# FPGA_Power.net
KiCad netlist of a schematic drawn in Altium Designer
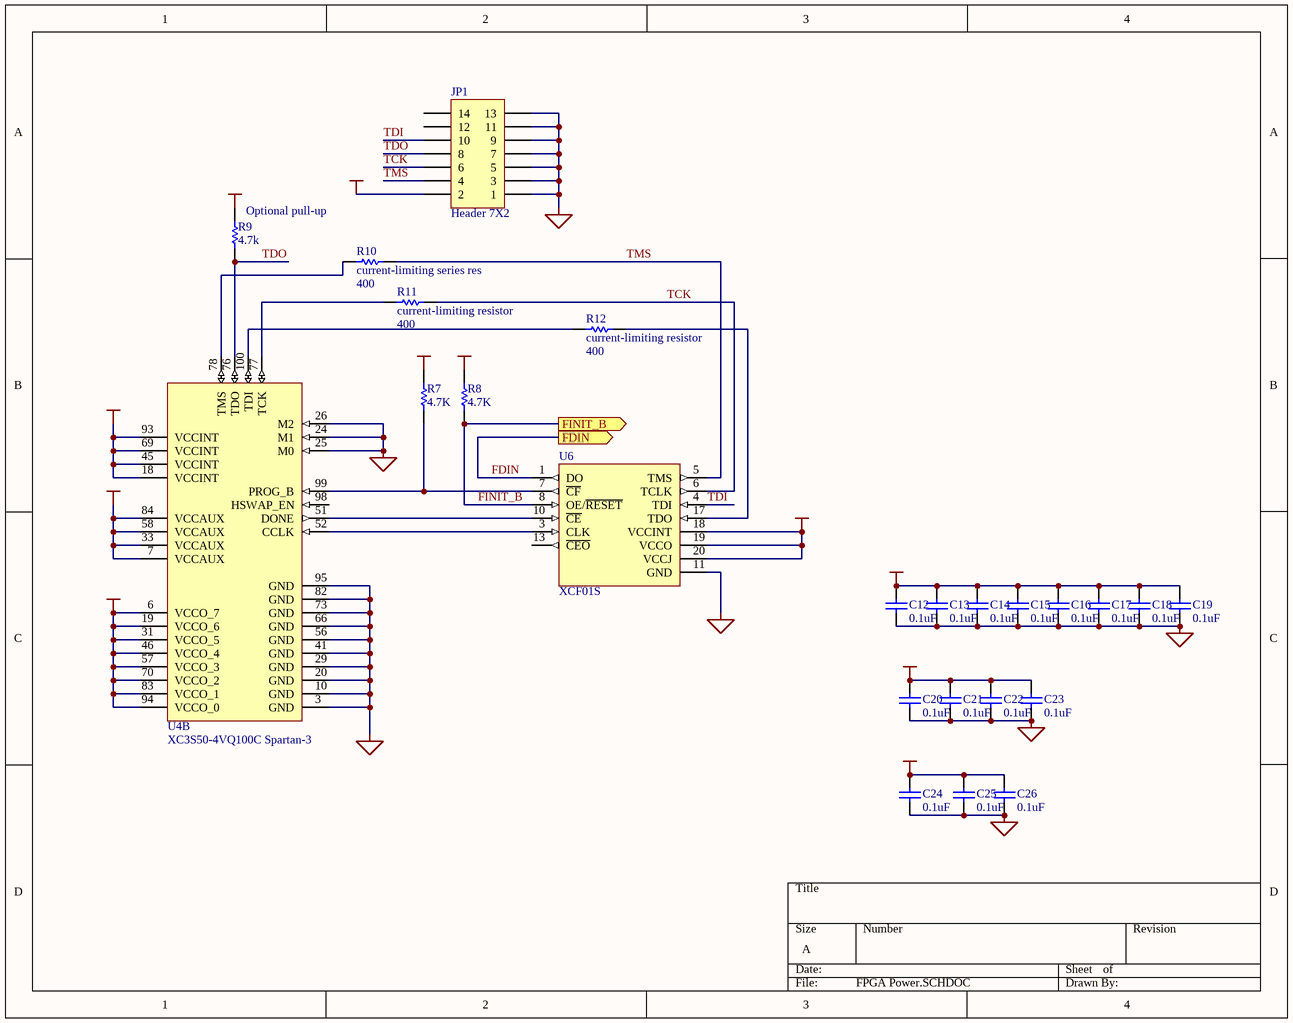
[diagram p0: FPGA Power.SCHDOC]

(export (version "E")
  (design (tool "Eeschema 10.0.6"))
  (components
    (comp (ref "C12")
      (value "0.1uF")
      (footprint "CC1608-0603")
      (description "Capacitor")
      (fields
        (field (name "MANUFACTURER") "Generic Components")
        (field (name "Comment") "Cap")
        (field (name "PUBLISHER") "Altium Limited")
      )
      (libsource (lib "Miscellaneous Devices") (part "Cap"))
    )
    (comp (ref "C13")
      (value "0.1uF")
      (footprint "CC1608-0603")
      (description "Capacitor")
      (fields
        (field (name "MANUFACTURER") "Generic Components")
        (field (name "Comment") "Cap")
        (field (name "PUBLISHER") "Altium Limited")
      )
      (libsource (lib "Miscellaneous Devices") (part "Cap"))
    )
    (comp (ref "C14")
      (value "0.1uF")
      (footprint "CC1608-0603")
      (description "Capacitor")
      (fields
        (field (name "MANUFACTURER") "Generic Components")
        (field (name "Comment") "Cap")
        (field (name "PUBLISHER") "Altium Limited")
      )
      (libsource (lib "Miscellaneous Devices") (part "Cap"))
    )
    (comp (ref "C15")
      (value "0.1uF")
      (footprint "CC1608-0603")
      (description "Capacitor")
      (fields
        (field (name "MANUFACTURER") "Generic Components")
        (field (name "Comment") "Cap")
        (field (name "PUBLISHER") "Altium Limited")
      )
      (libsource (lib "Miscellaneous Devices") (part "Cap"))
    )
    (comp (ref "C16")
      (value "0.1uF")
      (footprint "CC1608-0603")
      (description "Capacitor")
      (fields
        (field (name "MANUFACTURER") "Generic Components")
        (field (name "Comment") "Cap")
        (field (name "PUBLISHER") "Altium Limited")
      )
      (libsource (lib "Miscellaneous Devices") (part "Cap"))
    )
    (comp (ref "C17")
      (value "0.1uF")
      (footprint "CC1608-0603")
      (description "Capacitor")
      (fields
        (field (name "MANUFACTURER") "Generic Components")
        (field (name "Comment") "Cap")
        (field (name "PUBLISHER") "Altium Limited")
      )
      (libsource (lib "Miscellaneous Devices") (part "Cap"))
    )
    (comp (ref "C18")
      (value "0.1uF")
      (footprint "CC1608-0603")
      (description "Capacitor")
      (fields
        (field (name "MANUFACTURER") "Generic Components")
        (field (name "Comment") "Cap")
        (field (name "PUBLISHER") "Altium Limited")
      )
      (libsource (lib "Miscellaneous Devices") (part "Cap"))
    )
    (comp (ref "C19")
      (value "0.1uF")
      (footprint "CC1608-0603")
      (description "Capacitor")
      (fields
        (field (name "MANUFACTURER") "Generic Components")
        (field (name "Comment") "Cap")
        (field (name "PUBLISHER") "Altium Limited")
      )
      (libsource (lib "Miscellaneous Devices") (part "Cap"))
    )
    (comp (ref "C20")
      (value "0.1uF")
      (footprint "CC1608-0603")
      (description "Capacitor")
      (fields
        (field (name "MANUFACTURER") "Generic Components")
        (field (name "Comment") "Cap")
        (field (name "PUBLISHER") "Altium Limited")
      )
      (libsource (lib "Miscellaneous Devices") (part "Cap"))
    )
    (comp (ref "C21")
      (value "0.1uF")
      (footprint "CC1608-0603")
      (description "Capacitor")
      (fields
        (field (name "MANUFACTURER") "Generic Components")
        (field (name "Comment") "Cap")
        (field (name "PUBLISHER") "Altium Limited")
      )
      (libsource (lib "Miscellaneous Devices") (part "Cap"))
    )
    (comp (ref "C22")
      (value "0.1uF")
      (footprint "CC1608-0603")
      (description "Capacitor")
      (fields
        (field (name "MANUFACTURER") "Generic Components")
        (field (name "Comment") "Cap")
        (field (name "PUBLISHER") "Altium Limited")
      )
      (libsource (lib "Miscellaneous Devices") (part "Cap"))
    )
    (comp (ref "C23")
      (value "0.1uF")
      (footprint "CC1608-0603")
      (description "Capacitor")
      (fields
        (field (name "MANUFACTURER") "Generic Components")
        (field (name "Comment") "Cap")
        (field (name "PUBLISHER") "Altium Limited")
      )
      (libsource (lib "Miscellaneous Devices") (part "Cap"))
    )
    (comp (ref "C24")
      (value "0.1uF")
      (footprint "CC1608-0603")
      (description "Capacitor")
      (fields
        (field (name "MANUFACTURER") "Generic Components")
        (field (name "Comment") "Cap")
        (field (name "PUBLISHER") "Altium Limited")
      )
      (libsource (lib "Miscellaneous Devices") (part "Cap"))
    )
    (comp (ref "C25")
      (value "0.1uF")
      (footprint "CC1608-0603")
      (description "Capacitor")
      (fields
        (field (name "MANUFACTURER") "Generic Components")
        (field (name "Comment") "Cap")
        (field (name "PUBLISHER") "Altium Limited")
      )
      (libsource (lib "Miscellaneous Devices") (part "Cap"))
    )
    (comp (ref "C26")
      (value "0.1uF")
      (footprint "CC1608-0603")
      (description "Capacitor")
      (fields
        (field (name "MANUFACTURER") "Generic Components")
        (field (name "Comment") "Cap")
        (field (name "PUBLISHER") "Altium Limited")
      )
      (libsource (lib "Miscellaneous Devices") (part "Cap"))
    )
    (comp (ref "JP1")
      (value "Header 7X2")
      (footprint "HDR2x7-2mm")
      (description "Header, 7-Pin, Dual row")
      (fields (field (name "MANUFACTURER") "Generic Components") (field (name "PUBLISHER") "Altium Limited"))
      (libsource (lib "Miscellaneous Connectors") (part "Header 7X2"))
    )
    (comp (ref "R7")
      (value "4.7K")
      (footprint "CC1608-0603")
      (description "Resistor")
      (fields
        (field (name "MANUFACTURER") "Generic Components")
        (field (name "Comment") "Res1")
        (field (name "PUBLISHER") "Altium Limited")
      )
      (libsource (lib "Miscellaneous Devices") (part "Res1"))
    )
    (comp (ref "R8")
      (value "4.7K")
      (footprint "CC1608-0603")
      (description "Resistor")
      (fields
        (field (name "MANUFACTURER") "Generic Components")
        (field (name "Comment") "Res1")
        (field (name "PUBLISHER") "Altium Limited")
      )
      (libsource (lib "Miscellaneous Devices") (part "Res1"))
    )
    (comp (ref "R9")
      (value "Optional pull-up")
      (footprint "CC1608-0603")
      (description "Resistor")
      (fields
        (field (name "MANUFACTURER") "Generic Components")
        (field (name "ALTIUM_VALUE") "4.7k")
        (field (name "PUBLISHER") "Altium Limited")
      )
      (libsource (lib "Miscellaneous Devices") (part "Res1"))
    )
    (comp (ref "R10")
      (value "current-limiting series res")
      (footprint "CC1608-0603")
      (description "Resistor")
      (fields
        (field (name "MANUFACTURER") "Generic Components")
        (field (name "ALTIUM_VALUE") "400")
        (field (name "PUBLISHER") "Altium Limited")
      )
      (libsource (lib "Miscellaneous Devices") (part "Res1"))
    )
    (comp (ref "R11")
      (value "current-limiting resistor")
      (footprint "CC1608-0603")
      (description "Resistor")
      (fields
        (field (name "MANUFACTURER") "Generic Components")
        (field (name "ALTIUM_VALUE") "400")
        (field (name "PUBLISHER") "Altium Limited")
      )
      (libsource (lib "Miscellaneous Devices") (part "Res1"))
    )
    (comp (ref "R12")
      (value "current-limiting resistor")
      (footprint "CC1608-0603")
      (description "Resistor")
      (fields
        (field (name "MANUFACTURER") "Generic Components")
        (field (name "ALTIUM_VALUE") "400")
        (field (name "PUBLISHER") "Altium Limited")
      )
      (libsource (lib "Miscellaneous Devices") (part "Res1"))
    )
    (comp (ref "U4")
      (value "XC3S50-4VQ100C Spartan-3")
      (footprint "F-QFP14X14-G100/N")
      (description "Xilinx Spartan-3 VQ100")
      (libsource (lib "parts") (part "XC3S50-4VQ100C"))
    )
    (comp (ref "U6")
      (value "XCF01S")
      (footprint "TSSO6x6-G20/X.3")
      (description "Xilinx Platform Flash")
      (libsource (lib "parts") (part "XCF01S"))
    )
  )
  (nets
    (net (code "1") (name "+1.2VCC") (class "Default")
      (node (ref "C20") (pin "1") (pinfunction "1_1") (pintype "passive"))
      (node (ref "C21") (pin "1") (pinfunction "1_1") (pintype "passive"))
      (node (ref "C22") (pin "1") (pinfunction "1_1") (pintype "passive"))
      (node (ref "C23") (pin "1") (pinfunction "1_1") (pintype "passive"))
      (node (ref "U4") (pin "18") (pinfunction "VCCINT_18") (pintype "power_in"))
      (node (ref "U4") (pin "45") (pinfunction "VCCINT_45") (pintype "power_in"))
      (node (ref "U4") (pin "69") (pinfunction "VCCINT_69") (pintype "power_in"))
      (node (ref "U4") (pin "93") (pinfunction "VCCINT_93") (pintype "power_in"))
    )
    (net (code "2") (name "+2.5VCC") (class "Default")
      (node (ref "C24") (pin "1") (pinfunction "1_1") (pintype "passive"))
      (node (ref "C25") (pin "1") (pinfunction "1_1") (pintype "passive"))
      (node (ref "C26") (pin "1") (pinfunction "1_1") (pintype "passive"))
      (node (ref "U4") (pin "33") (pinfunction "VCCAUX_33") (pintype "power_in"))
      (node (ref "U4") (pin "58") (pinfunction "VCCAUX_58") (pintype "power_in"))
      (node (ref "U4") (pin "7") (pinfunction "VCCAUX_7") (pintype "power_in"))
      (node (ref "U4") (pin "84") (pinfunction "VCCAUX_84") (pintype "power_in"))
    )
    (net (code "3") (name "/FDIN") (class "Default")
      (node (ref "U6") (pin "1") (pinfunction "DO_1") (pintype "output"))
    )
    (net (code "4") (name "/FINIT_B") (class "Default")
      (node (ref "R8") (pin "1") (pinfunction "1_1") (pintype "passive"))
      (node (ref "U6") (pin "8") (pinfunction "OE/~{RESET}_8") (pintype "input"))
    )
    (net (code "5") (name "/TCK") (class "Default")
      (node (ref "JP1") (pin "6") (pinfunction "6_6") (pintype "passive"))
      (node (ref "R11") (pin "1") (pinfunction "1_1") (pintype "passive"))
      (node (ref "U6") (pin "6") (pinfunction "TCLK_6") (pintype "output"))
    )
    (net (code "6") (name "/TDI") (class "Default")
      (node (ref "JP1") (pin "10") (pinfunction "10_10") (pintype "passive"))
      (node (ref "U6") (pin "4") (pinfunction "TDI_4") (pintype "input"))
    )
    (net (code "7") (name "/TDO") (class "Default")
      (node (ref "JP1") (pin "8") (pinfunction "8_8") (pintype "passive"))
      (node (ref "R9") (pin "1") (pinfunction "1_1") (pintype "passive"))
      (node (ref "U4") (pin "76") (pinfunction "TDO_76") (pintype "bidirectional"))
    )
    (net (code "8") (name "/TMS") (class "Default")
      (node (ref "JP1") (pin "4") (pinfunction "4_4") (pintype "passive"))
      (node (ref "R10") (pin "1") (pinfunction "1_1") (pintype "passive"))
      (node (ref "U6") (pin "5") (pinfunction "TMS_5") (pintype "output"))
    )
    (net (code "9") (name "GND") (class "Default")
      (node (ref "C12") (pin "2") (pinfunction "2_2") (pintype "passive"))
      (node (ref "C13") (pin "2") (pinfunction "2_2") (pintype "passive"))
      (node (ref "C14") (pin "2") (pinfunction "2_2") (pintype "passive"))
      (node (ref "C15") (pin "2") (pinfunction "2_2") (pintype "passive"))
      (node (ref "C16") (pin "2") (pinfunction "2_2") (pintype "passive"))
      (node (ref "C17") (pin "2") (pinfunction "2_2") (pintype "passive"))
      (node (ref "C18") (pin "2") (pinfunction "2_2") (pintype "passive"))
      (node (ref "C19") (pin "2") (pinfunction "2_2") (pintype "passive"))
      (node (ref "C20") (pin "2") (pinfunction "2_2") (pintype "passive"))
      (node (ref "C21") (pin "2") (pinfunction "2_2") (pintype "passive"))
      (node (ref "C22") (pin "2") (pinfunction "2_2") (pintype "passive"))
      (node (ref "C23") (pin "2") (pinfunction "2_2") (pintype "passive"))
      (node (ref "C24") (pin "2") (pinfunction "2_2") (pintype "passive"))
      (node (ref "C25") (pin "2") (pinfunction "2_2") (pintype "passive"))
      (node (ref "C26") (pin "2") (pinfunction "2_2") (pintype "passive"))
      (node (ref "JP1") (pin "1") (pinfunction "1_1") (pintype "passive"))
      (node (ref "JP1") (pin "11") (pinfunction "11_11") (pintype "passive"))
      (node (ref "JP1") (pin "13") (pinfunction "13_13") (pintype "passive"))
      (node (ref "JP1") (pin "3") (pinfunction "3_3") (pintype "passive"))
      (node (ref "JP1") (pin "5") (pinfunction "5_5") (pintype "passive"))
      (node (ref "JP1") (pin "7") (pinfunction "7_7") (pintype "passive"))
      (node (ref "JP1") (pin "9") (pinfunction "9_9") (pintype "passive"))
      (node (ref "U4") (pin "10") (pinfunction "GND_10") (pintype "power_in"))
      (node (ref "U4") (pin "20") (pinfunction "GND_20") (pintype "power_in"))
      (node (ref "U4") (pin "24") (pinfunction "M1_24") (pintype "input"))
      (node (ref "U4") (pin "25") (pinfunction "M0_25") (pintype "input"))
      (node (ref "U4") (pin "26") (pinfunction "M2_26") (pintype "input"))
      (node (ref "U4") (pin "29") (pinfunction "GND_29") (pintype "power_in"))
      (node (ref "U4") (pin "3") (pinfunction "GND_3") (pintype "power_in"))
      (node (ref "U4") (pin "41") (pinfunction "GND_41") (pintype "power_in"))
      (node (ref "U4") (pin "56") (pinfunction "GND_56") (pintype "power_in"))
      (node (ref "U4") (pin "66") (pinfunction "GND_66") (pintype "power_in"))
      (node (ref "U4") (pin "73") (pinfunction "GND_73") (pintype "power_in"))
      (node (ref "U4") (pin "82") (pinfunction "GND_82") (pintype "power_in"))
      (node (ref "U4") (pin "95") (pinfunction "GND_95") (pintype "power_in"))
      (node (ref "U6") (pin "11") (pinfunction "GND_11") (pintype "power_in"))
    )
    (net (code "10") (name "Net-(U4B-CCLK)") (class "Default")
      (node (ref "U4") (pin "52") (pinfunction "CCLK_52") (pintype "input"))
      (node (ref "U6") (pin "3") (pinfunction "CLK_3") (pintype "input"))
    )
    (net (code "11") (name "Net-(U4B-DONE)") (class "Default")
      (node (ref "U4") (pin "51") (pinfunction "DONE_51") (pintype "output"))
      (node (ref "U6") (pin "10") (pinfunction "~{CE}_10") (pintype "input"))
    )
    (net (code "12") (name "Net-(U4B-PROG_B)") (class "Default")
      (node (ref "R7") (pin "1") (pinfunction "1_1") (pintype "passive"))
      (node (ref "U4") (pin "99") (pinfunction "PROG_B_99") (pintype "input"))
      (node (ref "U6") (pin "7") (pinfunction "~{CF}_7") (pintype "output"))
    )
    (net (code "13") (name "Net-(U4B-TCK)") (class "Default")
      (node (ref "R11") (pin "2") (pinfunction "2_2") (pintype "passive"))
      (node (ref "U4") (pin "77") (pinfunction "TCK_77") (pintype "bidirectional"))
    )
    (net (code "14") (name "Net-(U4B-TDI)") (class "Default")
      (node (ref "R12") (pin "2") (pinfunction "2_2") (pintype "passive"))
      (node (ref "U4") (pin "100") (pinfunction "TDI_100") (pintype "bidirectional"))
    )
    (net (code "15") (name "Net-(U4B-TMS)") (class "Default")
      (node (ref "R10") (pin "2") (pinfunction "2_2") (pintype "passive"))
      (node (ref "U4") (pin "78") (pinfunction "TMS_78") (pintype "bidirectional"))
    )
    (net (code "16") (name "Net-(U6-TDO)") (class "Default")
      (node (ref "R12") (pin "1") (pinfunction "1_1") (pintype "passive"))
      (node (ref "U6") (pin "17") (pinfunction "TDO_17") (pintype "input"))
    )
    (net (code "17") (name "VCC") (class "Default")
      (node (ref "C12") (pin "1") (pinfunction "1_1") (pintype "passive"))
      (node (ref "C13") (pin "1") (pinfunction "1_1") (pintype "passive"))
      (node (ref "C14") (pin "1") (pinfunction "1_1") (pintype "passive"))
      (node (ref "C15") (pin "1") (pinfunction "1_1") (pintype "passive"))
      (node (ref "C16") (pin "1") (pinfunction "1_1") (pintype "passive"))
      (node (ref "C17") (pin "1") (pinfunction "1_1") (pintype "passive"))
      (node (ref "C18") (pin "1") (pinfunction "1_1") (pintype "passive"))
      (node (ref "C19") (pin "1") (pinfunction "1_1") (pintype "passive"))
      (node (ref "JP1") (pin "2") (pinfunction "2_2") (pintype "passive"))
      (node (ref "R7") (pin "2") (pinfunction "2_2") (pintype "passive"))
      (node (ref "R8") (pin "2") (pinfunction "2_2") (pintype "passive"))
      (node (ref "R9") (pin "2") (pinfunction "2_2") (pintype "passive"))
      (node (ref "U4") (pin "19") (pinfunction "VCCO_6_19") (pintype "power_in"))
      (node (ref "U4") (pin "31") (pinfunction "VCCO_5_31") (pintype "power_in"))
      (node (ref "U4") (pin "46") (pinfunction "VCCO_4_46") (pintype "power_in"))
      (node (ref "U4") (pin "57") (pinfunction "VCCO_3_57") (pintype "power_in"))
      (node (ref "U4") (pin "6") (pinfunction "VCCO_7_6") (pintype "power_in"))
      (node (ref "U4") (pin "70") (pinfunction "VCCO_2_70") (pintype "power_in"))
      (node (ref "U4") (pin "83") (pinfunction "VCCO_1_83") (pintype "power_in"))
      (node (ref "U4") (pin "94") (pinfunction "VCCO_0_94") (pintype "power_in"))
      (node (ref "U6") (pin "18") (pinfunction "VCCINT_18") (pintype "power_in"))
      (node (ref "U6") (pin "19") (pinfunction "VCCO_19") (pintype "power_in"))
      (node (ref "U6") (pin "20") (pinfunction "VCCJ_20") (pintype "power_in"))
    )
    (net (code "18") (name "unconnected-(JP1-Pad12)") (class "Default")
      (node (ref "JP1") (pin "12") (pinfunction "12_12") (pintype "passive"))
    )
    (net (code "19") (name "unconnected-(JP1-Pad14)") (class "Default")
      (node (ref "JP1") (pin "14") (pinfunction "14_14") (pintype "passive"))
    )
    (net (code "20") (name "unconnected-(U4B-HSWAP_EN-Pad98)") (class "Default")
      (node (ref "U4") (pin "98") (pinfunction "HSWAP_EN_98") (pintype "input"))
    )
    (net (code "21") (name "unconnected-(U6-~{CEO}-Pad13)") (class "Default")
      (node (ref "U6") (pin "13") (pinfunction "~{CEO}_13") (pintype "output"))
    )
  )
)
